# MCU.net
KiCad netlist of a schematic drawn in Altium Designer
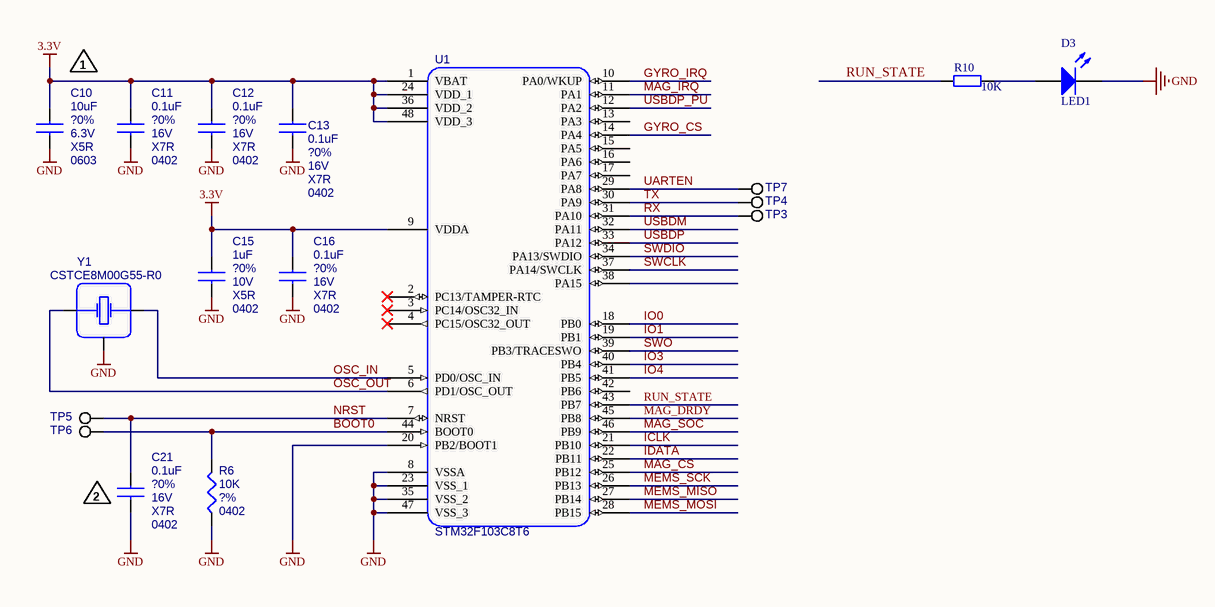
[diagram p0: MCU.SchDoc]

(export (version "E")
  (design (tool "Eeschema 10.0.6"))
  (components
    (comp (ref "C10")
      (value "10uF")
      (footprint "CAP_CERAMIC_0603")
      (description "CAP, CERAMIC, 10uF, ?0%, 6.3V, X5R, 0603")
      (fields
        (field (name "MANUFACTURER") "MURATA ELECTRONICS")
        (field (name "PART NUMBER") "GRM188R60J106ME47D")
        (field (name "TOLERANCE") "?0%")
        (field (name "VOLTAGE") "6.3V")
        (field (name "DIELECTRIC") "X5R")
        (field (name "PACKAGE") "0603")
      )
      (libsource (lib "TRACKER") (part "CAP, CERAMIC"))
    )
    (comp (ref "C11")
      (value "0.1uF")
      (footprint "CAP_CERAMIC_0402")
      (description "CAP, CERAMIC, 0.1uF, ?0%, 16V, X7R, 0402")
      (fields
        (field (name "MANUFACTURER") "MURATA ELECTRONICS")
        (field (name "PART NUMBER") "GRM155R71C104KA88D")
        (field (name "TOLERANCE") "?0%")
        (field (name "VOLTAGE") "16V")
        (field (name "DIELECTRIC") "X7R")
        (field (name "PACKAGE") "0402")
      )
      (libsource (lib "TRACKER") (part "CAP, CERAMIC"))
    )
    (comp (ref "C12")
      (value "0.1uF")
      (footprint "CAP_CERAMIC_0402")
      (description "CAP, CERAMIC, 0.1uF, ?0%, 16V, X7R, 0402")
      (fields
        (field (name "MANUFACTURER") "MURATA ELECTRONICS")
        (field (name "PART NUMBER") "GRM155R71C104KA88D")
        (field (name "TOLERANCE") "?0%")
        (field (name "VOLTAGE") "16V")
        (field (name "DIELECTRIC") "X7R")
        (field (name "PACKAGE") "0402")
      )
      (libsource (lib "TRACKER") (part "CAP, CERAMIC"))
    )
    (comp (ref "C13")
      (value "0.1uF")
      (footprint "GeekTechLib:CAP_0402")
      (description "CAP, CERAMIC, 0.1uF, ?0%, 16V, X7R, 0402")
      (fields
        (field (name "MANUFACTURER") "MURATA ELECTRONICS")
        (field (name "PART NUMBER") "GRM155R71C104KA88D")
        (field (name "TOLERANCE") "?0%")
        (field (name "VOLTAGE") "16V")
        (field (name "DIELECTRIC") "X7R")
        (field (name "PACKAGE") "0402")
      )
      (libsource (lib "GeekTechLib") (part "CAP, CERAMIC"))
    )
    (comp (ref "C15")
      (value "1uF")
      (footprint "CAP_CERAMIC_0402")
      (description "CAP, CERAMIC, 1uF, ?0%, 10V, X5R, 0402")
      (fields
        (field (name "MANUFACTURER") "MURATA ELECTRONICS")
        (field (name "PART NUMBER") "GRM155R61A105KE15D")
        (field (name "TOLERANCE") "?0%")
        (field (name "VOLTAGE") "10V")
        (field (name "DIELECTRIC") "X5R")
        (field (name "PACKAGE") "0402")
      )
      (libsource (lib "TRACKER") (part "CAP, CERAMIC"))
    )
    (comp (ref "C16")
      (value "0.1uF")
      (footprint "CAP_CERAMIC_0402")
      (description "CAP, CERAMIC, 0.1uF, ?0%, 16V, X7R, 0402")
      (fields
        (field (name "MANUFACTURER") "MURATA ELECTRONICS")
        (field (name "PART NUMBER") "GRM155R71C104KA88D")
        (field (name "TOLERANCE") "?0%")
        (field (name "VOLTAGE") "16V")
        (field (name "DIELECTRIC") "X7R")
        (field (name "PACKAGE") "0402")
      )
      (libsource (lib "TRACKER") (part "CAP, CERAMIC"))
    )
    (comp (ref "C21")
      (value "0.1uF")
      (footprint "CAP_CERAMIC_0402")
      (description "CAP, CERAMIC, 0.1uF, ?0%, 16V, X7R, 0402")
      (fields
        (field (name "MANUFACTURER") "MURATA ELECTRONICS")
        (field (name "PART NUMBER") "GRM155R71C104KA88D")
        (field (name "TOLERANCE") "?0%")
        (field (name "VOLTAGE") "16V")
        (field (name "DIELECTRIC") "X7R")
        (field (name "PACKAGE") "0402")
      )
      (libsource (lib "TRACKER") (part "CAP, CERAMIC"))
    )
    (comp (ref "D3")
      (value "LED1")
      (footprint "CAP_CERAMIC_0402")
      (description "Typical RED GaAs LED")
      (fields (field (name "PUBLISHER") "Altium Limited"))
      (libsource (lib "my1012") (part "LED1"))
    )
    (comp (ref "R6")
      (value "10K")
      (footprint "RESISTOR_0402")
      (description "RES, 10K OHM, 1/10W, ?%, 0402")
      (fields
        (field (name "MANUFACTURER") "PANASONIC")
        (field (name "PART NUMBER") "ERJ-2RKF1002X")
        (field (name "PACKAGE") "0402")
        (field (name "TOLERANCE") "?%")
      )
      (libsource (lib "TRACKER") (part "RESISTOR"))
    )
    (comp (ref "R10")
      (value "10K")
      (footprint "RESISTOR_0402")
      (description "Resistor")
      (fields (field (name "PUBLISHER") "Altium Limited"))
      (libsource (lib "my1012") (part "Res2"))
    )
    (comp (ref "TP3")
      (value "TEST POINT")
      (footprint "TEST_POINT_PAD")
      (libsource (lib "TRACKER") (part "TEST_POINT"))
    )
    (comp (ref "TP4")
      (value "TEST POINT")
      (footprint "TEST_POINT_PAD")
      (libsource (lib "TRACKER") (part "TEST_POINT"))
    )
    (comp (ref "TP5")
      (value "TEST POINT")
      (footprint "TEST_POINT_PAD")
      (libsource (lib "TRACKER") (part "TEST_POINT"))
    )
    (comp (ref "TP6")
      (value "TEST POINT")
      (footprint "TEST_POINT_PAD")
      (libsource (lib "TRACKER") (part "TEST_POINT"))
    )
    (comp (ref "TP7")
      (value "TEST POINT")
      (footprint "TEST_POINT_PAD")
      (libsource (lib "TRACKER") (part "TEST_POINT"))
    )
    (comp (ref "U1")
      (value "STM32F103C8T6")
      (footprint "LQFP48")
      (description "IC, STM32 MICROCONTROLLER, ARM CORTEX M3")
      (fields (field (name "MANUFACTURER") "ST MICROELECTRONICS"))
      (libsource (lib "TRACKER") (part "STM32F103C8T6"))
    )
    (comp (ref "Y1")
      (value "CSTCE8M00G55-R0")
      (footprint "CSTCE")
      (description "CERAMIC RESONATOR, 8MHz, +/-0.2%, 33pF, SMD")
      (fields (field (name "MANUFACTURER") "MURATA ELECTRONICS"))
      (libsource (lib "TRACKER") (part "CSTCE8M00G55-R0"))
    )
  )
  (nets
    (net (code "1") (name "/BOOT0") (class "Default")
      (node (ref "R6") (pin "2") (pinfunction "2_2") (pintype "passive"))
      (node (ref "TP6") (pin "1") (pinfunction "1_1") (pintype "passive"))
      (node (ref "U1") (pin "44") (pinfunction "BOOT0_44") (pintype "input"))
    )
    (net (code "2") (name "/GYRO_CS") (class "Default")
      (node (ref "U1") (pin "14") (pinfunction "PA4_14") (pintype "bidirectional"))
    )
    (net (code "3") (name "/GYRO_IRQ") (class "Default")
      (node (ref "U1") (pin "10") (pinfunction "PA0/WKUP_10") (pintype "bidirectional"))
    )
    (net (code "4") (name "/ICLK") (class "Default")
      (node (ref "U1") (pin "21") (pinfunction "PB10_21") (pintype "bidirectional"))
    )
    (net (code "5") (name "/IDATA") (class "Default")
      (node (ref "U1") (pin "22") (pinfunction "PB11_22") (pintype "bidirectional"))
    )
    (net (code "6") (name "/IO0") (class "Default")
      (node (ref "U1") (pin "18") (pinfunction "PB0_18") (pintype "bidirectional"))
    )
    (net (code "7") (name "/IO1") (class "Default")
      (node (ref "U1") (pin "19") (pinfunction "PB1_19") (pintype "bidirectional"))
    )
    (net (code "8") (name "/IO3") (class "Default")
      (node (ref "U1") (pin "40") (pinfunction "PB4_40") (pintype "bidirectional"))
    )
    (net (code "9") (name "/IO4") (class "Default")
      (node (ref "U1") (pin "41") (pinfunction "PB5_41") (pintype "bidirectional"))
    )
    (net (code "10") (name "/MAG_CS") (class "Default")
      (node (ref "U1") (pin "25") (pinfunction "PB12_25") (pintype "bidirectional"))
    )
    (net (code "11") (name "/MAG_DRDY") (class "Default")
      (node (ref "U1") (pin "45") (pinfunction "PB8_45") (pintype "bidirectional"))
    )
    (net (code "12") (name "/MAG_IRQ") (class "Default")
      (node (ref "U1") (pin "11") (pinfunction "PA1_11") (pintype "bidirectional"))
    )
    (net (code "13") (name "/MAG_SOC") (class "Default")
      (node (ref "U1") (pin "46") (pinfunction "PB9_46") (pintype "bidirectional"))
    )
    (net (code "14") (name "/MEMS_MISO") (class "Default")
      (node (ref "U1") (pin "27") (pinfunction "PB14_27") (pintype "bidirectional"))
    )
    (net (code "15") (name "/MEMS_MOSI") (class "Default")
      (node (ref "U1") (pin "28") (pinfunction "PB15_28") (pintype "bidirectional"))
    )
    (net (code "16") (name "/MEMS_SCK") (class "Default")
      (node (ref "U1") (pin "26") (pinfunction "PB13_26") (pintype "bidirectional"))
    )
    (net (code "17") (name "/NRST") (class "Default")
      (node (ref "C21") (pin "1") (pinfunction "1_1") (pintype "passive"))
      (node (ref "TP5") (pin "1") (pinfunction "1_1") (pintype "passive"))
      (node (ref "U1") (pin "7") (pinfunction "NRST_7") (pintype "bidirectional"))
    )
    (net (code "18") (name "/OSC_IN") (class "Default")
      (node (ref "U1") (pin "5") (pinfunction "PD0/OSC_IN_5") (pintype "input"))
      (node (ref "Y1") (pin "3") (pinfunction "3_3") (pintype "passive"))
    )
    (net (code "19") (name "/OSC_OUT") (class "Default")
      (node (ref "U1") (pin "6") (pinfunction "PD1/OSC_OUT_6") (pintype "output"))
      (node (ref "Y1") (pin "1") (pinfunction "1_1") (pintype "passive"))
    )
    (net (code "20") (name "/RUN_STATE") (class "Default")
      (node (ref "R10") (pin "2") (pinfunction "2_2") (pintype "passive"))
      (node (ref "U1") (pin "43") (pinfunction "PB7_43") (pintype "bidirectional"))
    )
    (net (code "21") (name "/RX") (class "Default")
      (node (ref "TP3") (pin "1") (pinfunction "1_1") (pintype "passive"))
      (node (ref "U1") (pin "31") (pinfunction "PA10_31") (pintype "bidirectional"))
    )
    (net (code "22") (name "/SWCLK") (class "Default")
      (node (ref "U1") (pin "37") (pinfunction "PA14/SWCLK_37") (pintype "bidirectional"))
    )
    (net (code "23") (name "/SWDIO") (class "Default")
      (node (ref "U1") (pin "34") (pinfunction "PA13/SWDIO_34") (pintype "bidirectional"))
    )
    (net (code "24") (name "/SWO") (class "Default")
      (node (ref "U1") (pin "39") (pinfunction "PB3/TRACESWO_39") (pintype "bidirectional"))
    )
    (net (code "25") (name "/TX") (class "Default")
      (node (ref "TP4") (pin "1") (pinfunction "1_1") (pintype "passive"))
      (node (ref "U1") (pin "30") (pinfunction "PA9_30") (pintype "bidirectional"))
    )
    (net (code "26") (name "/UARTEN") (class "Default")
      (node (ref "TP7") (pin "1") (pinfunction "1_1") (pintype "passive"))
      (node (ref "U1") (pin "29") (pinfunction "PA8_29") (pintype "bidirectional"))
    )
    (net (code "27") (name "/USBDM") (class "Default")
      (node (ref "U1") (pin "32") (pinfunction "PA11_32") (pintype "bidirectional"))
    )
    (net (code "28") (name "/USBDP") (class "Default")
      (node (ref "U1") (pin "33") (pinfunction "PA12_33") (pintype "bidirectional"))
    )
    (net (code "29") (name "/USBDP_PU") (class "Default")
      (node (ref "U1") (pin "12") (pinfunction "PA2_12") (pintype "bidirectional"))
    )
    (net (code "30") (name "3.3V") (class "Default")
      (node (ref "C10") (pin "1") (pinfunction "1_1") (pintype "passive"))
      (node (ref "C11") (pin "1") (pinfunction "1_1") (pintype "passive"))
      (node (ref "C12") (pin "1") (pinfunction "1_1") (pintype "passive"))
      (node (ref "C13") (pin "2") (pinfunction "2_2") (pintype "passive"))
      (node (ref "C15") (pin "1") (pinfunction "1_1") (pintype "passive"))
      (node (ref "C16") (pin "1") (pinfunction "1_1") (pintype "passive"))
      (node (ref "U1") (pin "1") (pinfunction "VBAT_1") (pintype "power_in"))
      (node (ref "U1") (pin "24") (pinfunction "VDD_1_24") (pintype "power_in"))
      (node (ref "U1") (pin "36") (pinfunction "VDD_2_36") (pintype "power_in"))
      (node (ref "U1") (pin "48") (pinfunction "VDD_3_48") (pintype "power_in"))
      (node (ref "U1") (pin "9") (pinfunction "VDDA_9") (pintype "power_in"))
    )
    (net (code "31") (name "GND") (class "Default")
      (node (ref "C10") (pin "2") (pinfunction "2_2") (pintype "passive"))
      (node (ref "C11") (pin "2") (pinfunction "2_2") (pintype "passive"))
      (node (ref "C12") (pin "2") (pinfunction "2_2") (pintype "passive"))
      (node (ref "C13") (pin "1") (pinfunction "1_1") (pintype "passive"))
      (node (ref "C15") (pin "2") (pinfunction "2_2") (pintype "passive"))
      (node (ref "C16") (pin "2") (pinfunction "2_2") (pintype "passive"))
      (node (ref "C21") (pin "2") (pinfunction "2_2") (pintype "passive"))
      (node (ref "D3") (pin "2") (pinfunction "K_2") (pintype "passive"))
      (node (ref "R6") (pin "1") (pinfunction "1_1") (pintype "passive"))
      (node (ref "U1") (pin "20") (pinfunction "PB2/BOOT1_20") (pintype "input"))
      (node (ref "U1") (pin "23") (pinfunction "VSS_1_23") (pintype "power_in"))
      (node (ref "U1") (pin "35") (pinfunction "VSS_2_35") (pintype "power_in"))
      (node (ref "U1") (pin "47") (pinfunction "VSS_3_47") (pintype "power_in"))
      (node (ref "U1") (pin "8") (pinfunction "VSSA_8") (pintype "power_in"))
      (node (ref "Y1") (pin "2") (pinfunction "GND_2") (pintype "power_in"))
    )
    (net (code "32") (name "Net-(D3-A)") (class "Default")
      (node (ref "D3") (pin "1") (pinfunction "A_1") (pintype "passive"))
      (node (ref "R10") (pin "1") (pinfunction "1_1") (pintype "passive"))
    )
    (net (code "33") (name "unconnected-(U1-PA3-Pad13)") (class "Default")
      (node (ref "U1") (pin "13") (pinfunction "PA3_13") (pintype "bidirectional"))
    )
    (net (code "34") (name "unconnected-(U1-PA5-Pad15)") (class "Default")
      (node (ref "U1") (pin "15") (pinfunction "PA5_15") (pintype "bidirectional"))
    )
    (net (code "35") (name "unconnected-(U1-PA6-Pad16)") (class "Default")
      (node (ref "U1") (pin "16") (pinfunction "PA6_16") (pintype "bidirectional"))
    )
    (net (code "36") (name "unconnected-(U1-PA7-Pad17)") (class "Default")
      (node (ref "U1") (pin "17") (pinfunction "PA7_17") (pintype "bidirectional"))
    )
    (net (code "37") (name "unconnected-(U1-PA15-Pad38)") (class "Default")
      (node (ref "U1") (pin "38") (pinfunction "PA15_38") (pintype "bidirectional"))
    )
    (net (code "38") (name "unconnected-(U1-PB6-Pad42)") (class "Default")
      (node (ref "U1") (pin "42") (pinfunction "PB6_42") (pintype "bidirectional"))
    )
    (net (code "39") (name "unconnected-(U1-PC13{slash}TAMPER-RTC-Pad2)") (class "Default")
      (node (ref "U1") (pin "2") (pinfunction "PC13/TAMPER-RTC_2") (pintype "bidirectional+no_connect"))
    )
    (net (code "40") (name "unconnected-(U1-PC14{slash}OSC32_IN-Pad3)") (class "Default")
      (node (ref "U1") (pin "3") (pinfunction "PC14/OSC32_IN_3") (pintype "input+no_connect"))
    )
    (net (code "41") (name "unconnected-(U1-PC15{slash}OSC32_OUT-Pad4)") (class "Default")
      (node (ref "U1") (pin "4") (pinfunction "PC15/OSC32_OUT_4") (pintype "output+no_connect"))
    )
  )
)
